# in4_single_v0_1.net
KiCad netlist of a schematic drawn in EAGLE
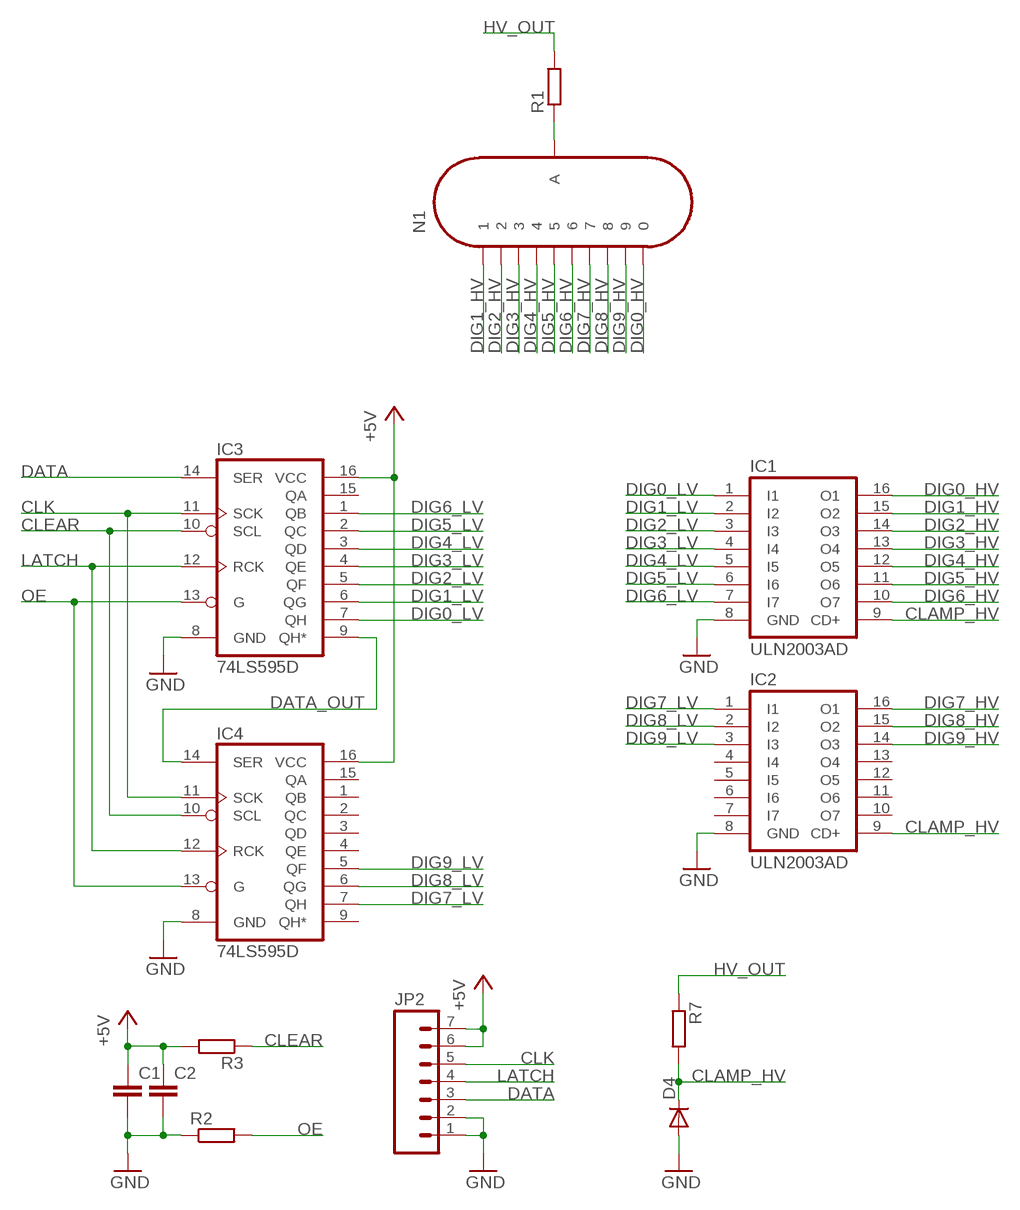
[diagram p0: schematic, sheet 1]
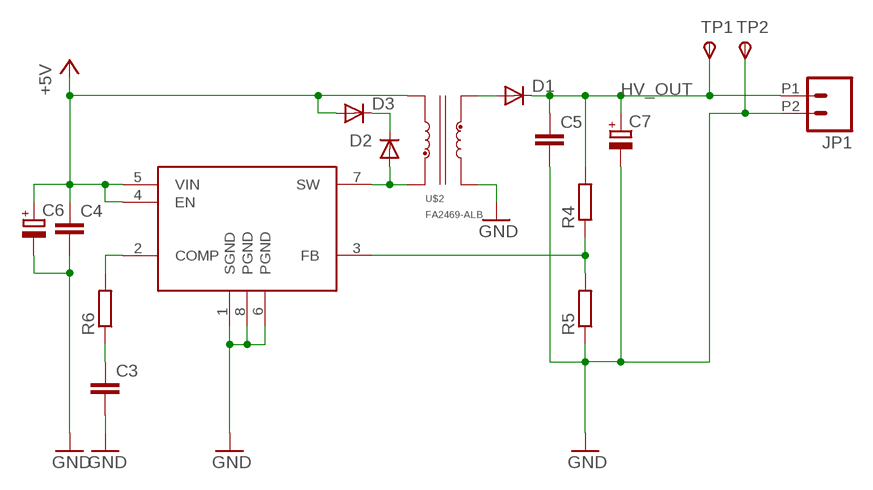
[diagram p1: schematic, sheet 2]

(export (version "E")
  (design (tool "Eeschema 10.0.6"))
  (components
    (comp (ref "C3")
      (value "C-EUC0805")
      (footprint "eagle-import:C0805")
      (libsource (lib "eagle-import") (part "C-EUC0805"))
    )
    (comp (ref "C4")
      (value "C-EUC1210")
      (footprint "eagle-import:C1210")
      (libsource (lib "eagle-import") (part "C-EUC1210"))
    )
    (comp (ref "C5")
      (value "C-EUC1210")
      (footprint "eagle-import:C1210")
      (libsource (lib "eagle-import") (part "C-EUC1210"))
    )
    (comp (ref "C6")
      (value "CPOL-EUE2.5-5")
      (footprint "eagle-import:E2,5-5")
      (libsource (lib "eagle-import") (part "CPOL-EUE2.5-5"))
    )
    (comp (ref "C7")
      (value "CPOL-EUE2.5-5")
      (footprint "eagle-import:E2,5-5")
      (libsource (lib "eagle-import") (part "CPOL-EUE2.5-5"))
    )
    (comp (ref "D1")
      (value "DIODE-DO-214AC")
      (footprint "eagle-import:DO-214AC")
      (libsource (lib "eagle-import") (part "DIODE-DO-214AC"))
    )
    (comp (ref "D2")
      (value "DIODE-SOD-123")
      (footprint "eagle-import:SOD-123")
      (libsource (lib "eagle-import") (part "DIODE-SOD-123"))
    )
    (comp (ref "D3")
      (value "DIODE-SOD-123")
      (footprint "eagle-import:SOD-123")
      (libsource (lib "eagle-import") (part "DIODE-SOD-123"))
    )
    (comp (ref "IC5")
      (value "MC3172YM")
      (footprint "eagle-import:SOIC8")
      (libsource (lib "eagle-import") (part "MC3172YM"))
    )
    (comp (ref "JP1")
      (value "M022.54MM_SCREWTERM")
      (footprint "eagle-import:1X02_2.54_SCREWTERM")
      (libsource (lib "eagle-import") (part "M022.54MM_SCREWTERM"))
    )
    (comp (ref "R4")
      (value "R-EU_R0805")
      (footprint "eagle-import:R0805")
      (libsource (lib "eagle-import") (part "R-EU_R0805"))
    )
    (comp (ref "R5")
      (value "R-EU_R0805")
      (footprint "eagle-import:R0805")
      (libsource (lib "eagle-import") (part "R-EU_R0805"))
    )
    (comp (ref "R6")
      (value "R-EU_R0805")
      (footprint "eagle-import:R0805")
      (libsource (lib "eagle-import") (part "R-EU_R0805"))
    )
    (comp (ref "TP1")
      (value "TPSPAD1-13")
      (footprint "eagle-import:P1-13")
      (libsource (lib "eagle-import") (part "TPSPAD1-13"))
    )
    (comp (ref "TP2")
      (value "TPSPAD1-13")
      (footprint "eagle-import:P1-13")
      (libsource (lib "eagle-import") (part "TPSPAD1-13"))
    )
    (comp (ref "U$2")
      (value "FA2469-ALB")
      (footprint "eagle-import:FA2469")
      (libsource (lib "eagle-import") (part "FA2469-ALB"))
    )
    (comp (ref "C1")
      (value "C-EUC0805")
      (footprint "eagle-import:C0805")
      (libsource (lib "eagle-import") (part "C-EUC0805"))
    )
    (comp (ref "C2")
      (value "C-EUC0805")
      (footprint "eagle-import:C0805")
      (libsource (lib "eagle-import") (part "C-EUC0805"))
    )
    (comp (ref "D4")
      (value "DIODE-SOD-123")
      (footprint "eagle-import:SOD-123")
      (libsource (lib "eagle-import") (part "DIODE-SOD-123"))
    )
    (comp (ref "IC1")
      (value "ULN2003AD")
      (footprint "eagle-import:SO16")
      (libsource (lib "eagle-import") (part "ULN2003AD"))
    )
    (comp (ref "IC2")
      (value "ULN2003AD")
      (footprint "eagle-import:SO16")
      (libsource (lib "eagle-import") (part "ULN2003AD"))
    )
    (comp (ref "IC3")
      (value "74LS595D")
      (footprint "eagle-import:SO16")
      (libsource (lib "eagle-import") (part "74595DLS"))
    )
    (comp (ref "IC4")
      (value "74LS595D")
      (footprint "eagle-import:SO16")
      (fields (field (name "PROD_ID") "IC-07875"))
      (libsource (lib "eagle-import") (part "74595DLS"))
    )
    (comp (ref "JP2")
      (value "M07LOCK")
      (footprint "eagle-import:1X07_LOCK")
      (libsource (lib "eagle-import") (part "M07LOCK"))
    )
    (comp (ref "N1")
      (value "IN-4")
      (footprint "eagle-import:IN-4")
      (libsource (lib "eagle-import") (part "IN-4"))
    )
    (comp (ref "R1")
      (value "R-EU_0204/7")
      (footprint "eagle-import:0204_7")
      (libsource (lib "eagle-import") (part "resistor_R-EU_0204/7"))
    )
    (comp (ref "R2")
      (value "R-EU_R0805")
      (footprint "eagle-import:R0805")
      (libsource (lib "eagle-import") (part "R-EU_R0805"))
    )
    (comp (ref "R3")
      (value "R-EU_R0805")
      (footprint "eagle-import:R0805")
      (libsource (lib "eagle-import") (part "R-EU_R0805"))
    )
    (comp (ref "R7")
      (value "R-EU_R0805")
      (footprint "eagle-import:R0805")
      (libsource (lib "eagle-import") (part "R-EU_R0805"))
    )
  )
  (nets
    (net (code "1") (name "+5V") (class "Default")
      (node (ref "C1") (pin "1") (pinfunction "1_1") (pintype "passive"))
      (node (ref "C2") (pin "1") (pinfunction "1_1") (pintype "passive"))
      (node (ref "C4") (pin "1") (pinfunction "1_1") (pintype "passive"))
      (node (ref "C6") (pin "+") (pinfunction "+_+") (pintype "passive"))
      (node (ref "D3") (pin "A") (pinfunction "A_A") (pintype "passive"))
      (node (ref "IC3") (pin "16") (pinfunction "VCC_16") (pintype "power_in"))
      (node (ref "IC4") (pin "16") (pinfunction "VCC_16") (pintype "power_in"))
      (node (ref "IC5") (pin "4") (pinfunction "EN_4") (pintype "bidirectional"))
      (node (ref "IC5") (pin "5") (pinfunction "VIN_5") (pintype "bidirectional"))
      (node (ref "JP2") (pin "6") (pinfunction "6_6") (pintype "passive"))
      (node (ref "JP2") (pin "7") (pinfunction "7_7") (pintype "passive"))
      (node (ref "R3") (pin "2") (pinfunction "2_2") (pintype "passive"))
      (node (ref "U$2") (pin "3") (pinfunction "3_3") (pintype "passive"))
    )
    (net (code "2") (name "CLAMP_HV") (class "Default")
      (node (ref "D4") (pin "C") (pinfunction "C_C") (pintype "passive"))
      (node (ref "IC1") (pin "9") (pinfunction "CD+_9") (pintype "passive"))
      (node (ref "IC2") (pin "9") (pinfunction "CD+_9") (pintype "passive"))
      (node (ref "R7") (pin "2") (pinfunction "2_2") (pintype "passive"))
    )
    (net (code "3") (name "CLEAR") (class "Default")
      (node (ref "IC3") (pin "10") (pinfunction "SCL_10") (pintype "input"))
      (node (ref "IC4") (pin "10") (pinfunction "SCL_10") (pintype "input"))
      (node (ref "R3") (pin "1") (pinfunction "1_1") (pintype "passive"))
    )
    (net (code "4") (name "CLK") (class "Default")
      (node (ref "IC3") (pin "11") (pinfunction "SCK_11") (pintype "input"))
      (node (ref "IC4") (pin "11") (pinfunction "SCK_11") (pintype "input"))
      (node (ref "JP2") (pin "5") (pinfunction "5_5") (pintype "passive"))
    )
    (net (code "5") (name "DATA") (class "Default")
      (node (ref "IC3") (pin "14") (pinfunction "SER_14") (pintype "input"))
      (node (ref "JP2") (pin "3") (pinfunction "3_3") (pintype "passive"))
    )
    (net (code "6") (name "DATA_OUT") (class "Default")
      (node (ref "IC3") (pin "9") (pinfunction "QH*_9") (pintype "tri_state"))
      (node (ref "IC4") (pin "14") (pinfunction "SER_14") (pintype "input"))
    )
    (net (code "7") (name "DIG0_HV") (class "Default")
      (node (ref "IC1") (pin "16") (pinfunction "O1_16") (pintype "open_collector"))
      (node (ref "N1") (pin "8") (pinfunction "0_8") (pintype "bidirectional"))
    )
    (net (code "8") (name "DIG0_LV") (class "Default")
      (node (ref "IC1") (pin "1") (pinfunction "I1_1") (pintype "input"))
      (node (ref "IC3") (pin "7") (pinfunction "QH_7") (pintype "tri_state"))
    )
    (net (code "9") (name "DIG1_HV") (class "Default")
      (node (ref "IC1") (pin "15") (pinfunction "O2_15") (pintype "open_collector"))
      (node (ref "N1") (pin "14") (pinfunction "1_14") (pintype "bidirectional"))
    )
    (net (code "10") (name "DIG1_LV") (class "Default")
      (node (ref "IC1") (pin "2") (pinfunction "I2_2") (pintype "input"))
      (node (ref "IC3") (pin "6") (pinfunction "QG_6") (pintype "tri_state"))
    )
    (net (code "11") (name "DIG2_HV") (class "Default")
      (node (ref "IC1") (pin "14") (pinfunction "O3_14") (pintype "open_collector"))
      (node (ref "N1") (pin "9") (pinfunction "2_9") (pintype "bidirectional"))
    )
    (net (code "12") (name "DIG2_LV") (class "Default")
      (node (ref "IC1") (pin "3") (pinfunction "I3_3") (pintype "input"))
      (node (ref "IC3") (pin "5") (pinfunction "QF_5") (pintype "tri_state"))
    )
    (net (code "13") (name "DIG3_HV") (class "Default")
      (node (ref "IC1") (pin "13") (pinfunction "O4_13") (pintype "open_collector"))
      (node (ref "N1") (pin "11") (pinfunction "3_11") (pintype "bidirectional"))
    )
    (net (code "14") (name "DIG3_LV") (class "Default")
      (node (ref "IC1") (pin "4") (pinfunction "I4_4") (pintype "input"))
      (node (ref "IC3") (pin "4") (pinfunction "QE_4") (pintype "tri_state"))
    )
    (net (code "15") (name "DIG4_HV") (class "Default")
      (node (ref "IC1") (pin "12") (pinfunction "O5_12") (pintype "open_collector"))
      (node (ref "N1") (pin "1") (pinfunction "4_1") (pintype "bidirectional"))
    )
    (net (code "16") (name "DIG4_LV") (class "Default")
      (node (ref "IC1") (pin "5") (pinfunction "I5_5") (pintype "input"))
      (node (ref "IC3") (pin "3") (pinfunction "QD_3") (pintype "tri_state"))
    )
    (net (code "17") (name "DIG5_HV") (class "Default")
      (node (ref "IC1") (pin "11") (pinfunction "O6_11") (pintype "open_collector"))
      (node (ref "N1") (pin "12") (pinfunction "5_12") (pintype "bidirectional"))
    )
    (net (code "18") (name "DIG5_LV") (class "Default")
      (node (ref "IC1") (pin "6") (pinfunction "I6_6") (pintype "input"))
      (node (ref "IC3") (pin "2") (pinfunction "QC_2") (pintype "tri_state"))
    )
    (net (code "19") (name "DIG6_HV") (class "Default")
      (node (ref "IC1") (pin "10") (pinfunction "O7_10") (pintype "open_collector"))
      (node (ref "N1") (pin "2") (pinfunction "6_2") (pintype "bidirectional"))
    )
    (net (code "20") (name "DIG6_LV") (class "Default")
      (node (ref "IC1") (pin "7") (pinfunction "I7_7") (pintype "input"))
      (node (ref "IC3") (pin "1") (pinfunction "QB_1") (pintype "tri_state"))
    )
    (net (code "21") (name "DIG7_HV") (class "Default")
      (node (ref "IC2") (pin "16") (pinfunction "O1_16") (pintype "open_collector"))
      (node (ref "N1") (pin "6") (pinfunction "7_6") (pintype "bidirectional"))
    )
    (net (code "22") (name "DIG7_LV") (class "Default")
      (node (ref "IC2") (pin "1") (pinfunction "I1_1") (pintype "input"))
      (node (ref "IC4") (pin "7") (pinfunction "QH_7") (pintype "tri_state"))
    )
    (net (code "23") (name "DIG8_HV") (class "Default")
      (node (ref "IC2") (pin "15") (pinfunction "O2_15") (pintype "open_collector"))
      (node (ref "N1") (pin "3") (pinfunction "8_3") (pintype "bidirectional"))
    )
    (net (code "24") (name "DIG8_LV") (class "Default")
      (node (ref "IC2") (pin "2") (pinfunction "I2_2") (pintype "input"))
      (node (ref "IC4") (pin "6") (pinfunction "QG_6") (pintype "tri_state"))
    )
    (net (code "25") (name "DIG9_HV") (class "Default")
      (node (ref "IC2") (pin "14") (pinfunction "O3_14") (pintype "open_collector"))
      (node (ref "N1") (pin "5") (pinfunction "9_5") (pintype "bidirectional"))
    )
    (net (code "26") (name "DIG9_LV") (class "Default")
      (node (ref "IC2") (pin "3") (pinfunction "I3_3") (pintype "input"))
      (node (ref "IC4") (pin "5") (pinfunction "QF_5") (pintype "tri_state"))
    )
    (net (code "27") (name "GND") (class "Default")
      (node (ref "C1") (pin "2") (pinfunction "2_2") (pintype "passive"))
      (node (ref "C2") (pin "2") (pinfunction "2_2") (pintype "passive"))
      (node (ref "C3") (pin "2") (pinfunction "2_2") (pintype "passive"))
      (node (ref "C4") (pin "2") (pinfunction "2_2") (pintype "passive"))
      (node (ref "C5") (pin "2") (pinfunction "2_2") (pintype "passive"))
      (node (ref "C6") (pin "-") (pinfunction "-_-") (pintype "passive"))
      (node (ref "C7") (pin "-") (pinfunction "-_-") (pintype "passive"))
      (node (ref "D4") (pin "A") (pinfunction "A_A") (pintype "passive"))
      (node (ref "IC1") (pin "8") (pinfunction "GND_8") (pintype "power_in"))
      (node (ref "IC2") (pin "8") (pinfunction "GND_8") (pintype "power_in"))
      (node (ref "IC3") (pin "8") (pinfunction "GND_8") (pintype "power_in"))
      (node (ref "IC4") (pin "8") (pinfunction "GND_8") (pintype "power_in"))
      (node (ref "IC5") (pin "1") (pinfunction "SGND_1") (pintype "bidirectional"))
      (node (ref "IC5") (pin "6") (pinfunction "PGND_6") (pintype "bidirectional"))
      (node (ref "IC5") (pin "8") (pinfunction "PGND_8") (pintype "bidirectional"))
      (node (ref "JP1") (pin "P2") (pinfunction "2_P2") (pintype "passive"))
      (node (ref "JP2") (pin "1") (pinfunction "1_1") (pintype "passive"))
      (node (ref "JP2") (pin "2") (pinfunction "2_2") (pintype "passive"))
      (node (ref "R2") (pin "1") (pinfunction "1_1") (pintype "passive"))
      (node (ref "R5") (pin "1") (pinfunction "1_1") (pintype "passive"))
      (node (ref "TP2") (pin "TP") (pinfunction "PP_TP") (pintype "input"))
      (node (ref "U$2") (pin "6") (pinfunction "6_6") (pintype "passive"))
    )
    (net (code "28") (name "HV_OUT") (class "Default")
      (node (ref "C5") (pin "1") (pinfunction "1_1") (pintype "passive"))
      (node (ref "C7") (pin "+") (pinfunction "+_+") (pintype "passive"))
      (node (ref "D1") (pin "1") (pinfunction "C_1") (pintype "passive"))
      (node (ref "JP1") (pin "P1") (pinfunction "1_P1") (pintype "passive"))
      (node (ref "R1") (pin "2") (pinfunction "2_2") (pintype "passive"))
      (node (ref "R4") (pin "2") (pinfunction "2_2") (pintype "passive"))
      (node (ref "R7") (pin "1") (pinfunction "1_1") (pintype "passive"))
      (node (ref "TP1") (pin "TP") (pinfunction "PP_TP") (pintype "input"))
    )
    (net (code "29") (name "LATCH") (class "Default")
      (node (ref "IC3") (pin "12") (pinfunction "RCK_12") (pintype "input"))
      (node (ref "IC4") (pin "12") (pinfunction "RCK_12") (pintype "input"))
      (node (ref "JP2") (pin "4") (pinfunction "4_4") (pintype "passive"))
    )
    (net (code "30") (name "Net-(C3-Pad1)") (class "Default")
      (node (ref "C3") (pin "1") (pinfunction "1_1") (pintype "passive"))
      (node (ref "R6") (pin "1") (pinfunction "1_1") (pintype "passive"))
    )
    (net (code "31") (name "Net-(D1-A)") (class "Default")
      (node (ref "D1") (pin "2") (pinfunction "A_2") (pintype "passive"))
      (node (ref "U$2") (pin "4") (pinfunction "4_4") (pintype "passive"))
    )
    (net (code "32") (name "Net-(D2-PadC)") (class "Default")
      (node (ref "D2") (pin "C") (pinfunction "C_C") (pintype "passive"))
      (node (ref "D3") (pin "C") (pinfunction "C_C") (pintype "passive"))
    )
    (net (code "33") (name "Net-(IC5-COMP)") (class "Default")
      (node (ref "IC5") (pin "2") (pinfunction "COMP_2") (pintype "bidirectional"))
      (node (ref "R6") (pin "2") (pinfunction "2_2") (pintype "passive"))
    )
    (net (code "34") (name "Net-(IC5-FB)") (class "Default")
      (node (ref "IC5") (pin "3") (pinfunction "FB_3") (pintype "bidirectional"))
      (node (ref "R4") (pin "1") (pinfunction "1_1") (pintype "passive"))
      (node (ref "R5") (pin "2") (pinfunction "2_2") (pintype "passive"))
    )
    (net (code "35") (name "Net-(IC5-SW)") (class "Default")
      (node (ref "D2") (pin "A") (pinfunction "A_A") (pintype "passive"))
      (node (ref "IC5") (pin "7") (pinfunction "SW_7") (pintype "bidirectional"))
      (node (ref "U$2") (pin "1") (pinfunction "1_1") (pintype "passive"))
    )
    (net (code "36") (name "Net-(N1-A)") (class "Default")
      (node (ref "N1") (pin "4") (pinfunction "A_4") (pintype "bidirectional"))
      (node (ref "R1") (pin "1") (pinfunction "1_1") (pintype "passive"))
    )
    (net (code "37") (name "OE") (class "Default")
      (node (ref "IC3") (pin "13") (pinfunction "G_13") (pintype "input"))
      (node (ref "IC4") (pin "13") (pinfunction "G_13") (pintype "input"))
      (node (ref "R2") (pin "2") (pinfunction "2_2") (pintype "passive"))
    )
    (net (code "38") (name "unconnected-(IC2-I4-Pad4)") (class "Default")
      (node (ref "IC2") (pin "4") (pinfunction "I4_4") (pintype "input"))
    )
    (net (code "39") (name "unconnected-(IC2-I5-Pad5)") (class "Default")
      (node (ref "IC2") (pin "5") (pinfunction "I5_5") (pintype "input"))
    )
    (net (code "40") (name "unconnected-(IC2-I6-Pad6)") (class "Default")
      (node (ref "IC2") (pin "6") (pinfunction "I6_6") (pintype "input"))
    )
    (net (code "41") (name "unconnected-(IC2-I7-Pad7)") (class "Default")
      (node (ref "IC2") (pin "7") (pinfunction "I7_7") (pintype "input"))
    )
    (net (code "42") (name "unconnected-(IC2-O4-Pad13)") (class "Default")
      (node (ref "IC2") (pin "13") (pinfunction "O4_13") (pintype "open_collector"))
    )
    (net (code "43") (name "unconnected-(IC2-O5-Pad12)") (class "Default")
      (node (ref "IC2") (pin "12") (pinfunction "O5_12") (pintype "open_collector"))
    )
    (net (code "44") (name "unconnected-(IC2-O6-Pad11)") (class "Default")
      (node (ref "IC2") (pin "11") (pinfunction "O6_11") (pintype "open_collector"))
    )
    (net (code "45") (name "unconnected-(IC2-O7-Pad10)") (class "Default")
      (node (ref "IC2") (pin "10") (pinfunction "O7_10") (pintype "open_collector"))
    )
    (net (code "46") (name "unconnected-(IC3-QA-Pad15)") (class "Default")
      (node (ref "IC3") (pin "15") (pinfunction "QA_15") (pintype "tri_state"))
    )
    (net (code "47") (name "unconnected-(IC4-QA-Pad15)") (class "Default")
      (node (ref "IC4") (pin "15") (pinfunction "QA_15") (pintype "tri_state"))
    )
    (net (code "48") (name "unconnected-(IC4-QB-Pad1)") (class "Default")
      (node (ref "IC4") (pin "1") (pinfunction "QB_1") (pintype "tri_state"))
    )
    (net (code "49") (name "unconnected-(IC4-QC-Pad2)") (class "Default")
      (node (ref "IC4") (pin "2") (pinfunction "QC_2") (pintype "tri_state"))
    )
    (net (code "50") (name "unconnected-(IC4-QD-Pad3)") (class "Default")
      (node (ref "IC4") (pin "3") (pinfunction "QD_3") (pintype "tri_state"))
    )
    (net (code "51") (name "unconnected-(IC4-QE-Pad4)") (class "Default")
      (node (ref "IC4") (pin "4") (pinfunction "QE_4") (pintype "tri_state"))
    )
    (net (code "52") (name "unconnected-(IC4-QH*-Pad9)") (class "Default")
      (node (ref "IC4") (pin "9") (pinfunction "QH*_9") (pintype "tri_state"))
    )
  )
)
